# led-cpu-rev2.net
KiCad netlist of a schematic drawn in EAGLE
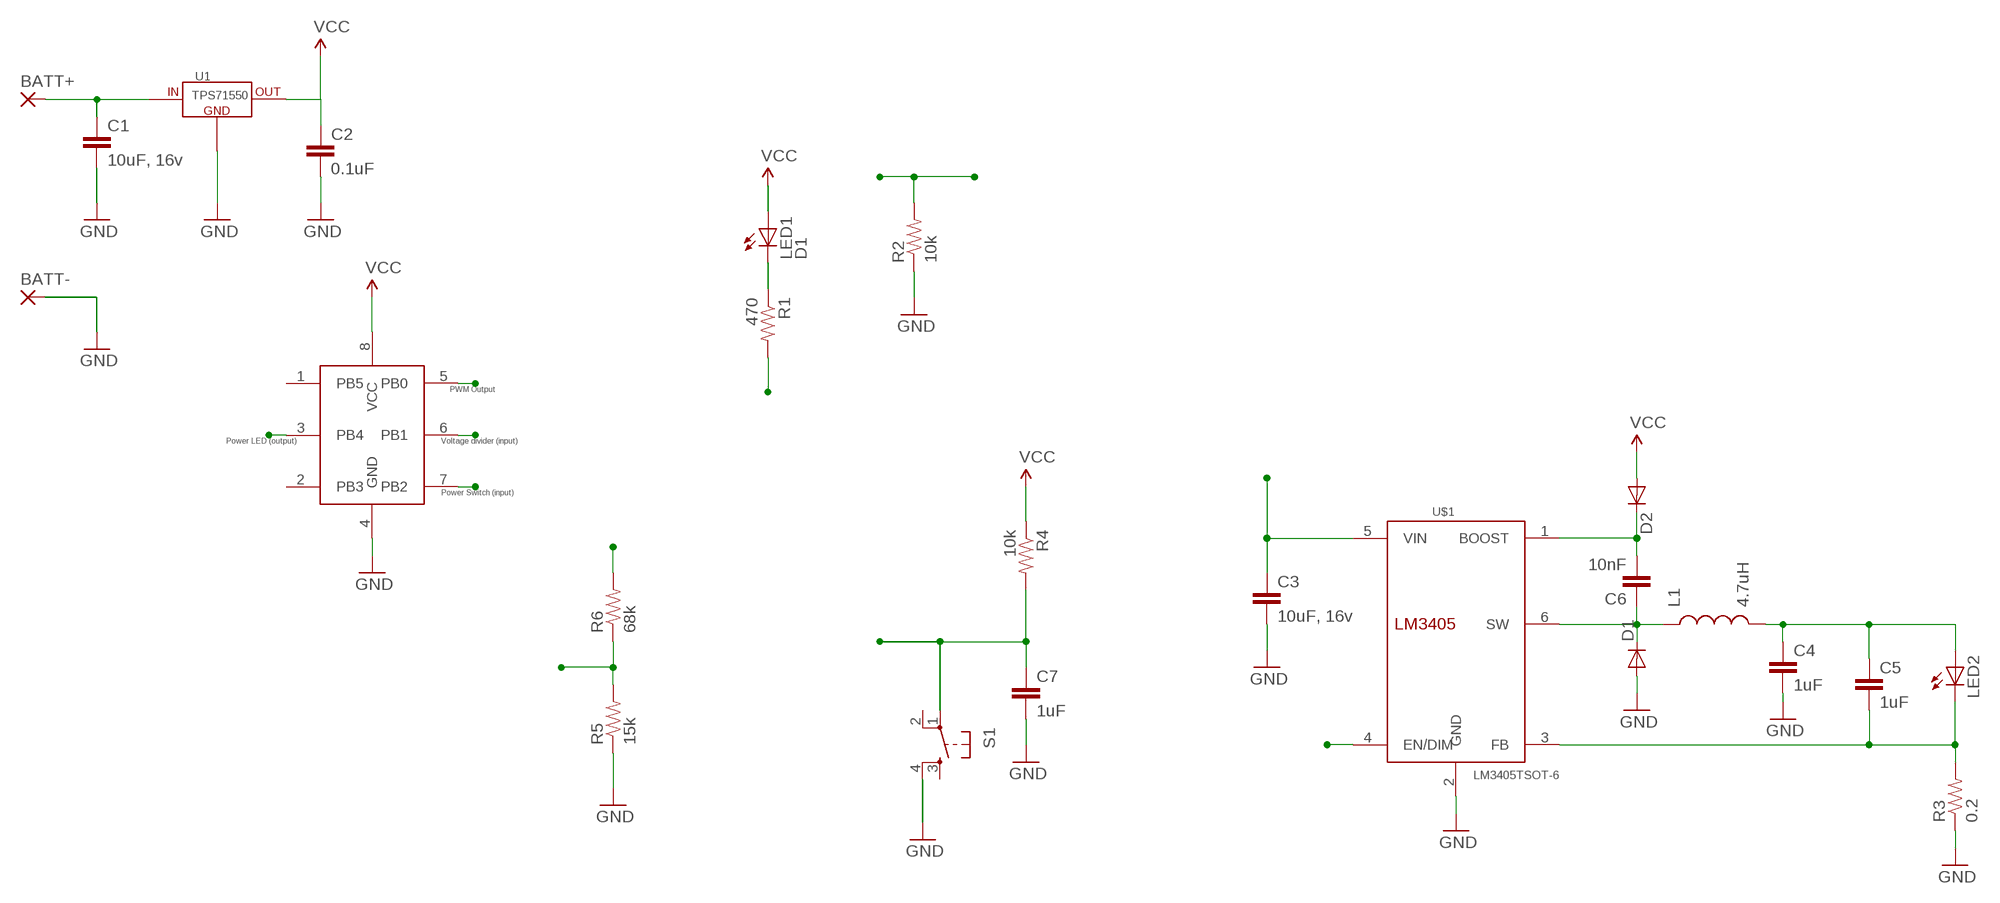
[diagram p0: schematic, sheet 1]

(export (version "E")
  (design (tool "Eeschema 10.0.6"))
  (components
    (comp (ref "BATT+")
      (value "SMD5")
      (footprint "eagle-import:SMD2,54-5,08")
      (libsource (lib "eagle-import") (part "SMD5"))
    )
    (comp (ref "BATT-")
      (value "SMD5")
      (footprint "eagle-import:SMD2,54-5,08")
      (libsource (lib "eagle-import") (part "SMD5"))
    )
    (comp (ref "C1")
      (value "10uF, 16v")
      (footprint "eagle-import:0805")
      (libsource (lib "eagle-import") (part "CAP0805"))
    )
    (comp (ref "C2")
      (value "0.1uF")
      (footprint "eagle-import:0805")
      (libsource (lib "eagle-import") (part "CAP0805"))
    )
    (comp (ref "C3")
      (value "10uF, 16v")
      (footprint "eagle-import:0805")
      (libsource (lib "eagle-import") (part "CAP0805"))
    )
    (comp (ref "C4")
      (value "1uF")
      (footprint "eagle-import:1206")
      (libsource (lib "eagle-import") (part "CAP1206"))
    )
    (comp (ref "C5")
      (value "1uF")
      (footprint "eagle-import:1206")
      (libsource (lib "eagle-import") (part "CAP1206"))
    )
    (comp (ref "C6")
      (value "10nF")
      (footprint "eagle-import:0805")
      (libsource (lib "eagle-import") (part "CAP0805"))
    )
    (comp (ref "C7")
      (value "1uF")
      (footprint "eagle-import:0805")
      (libsource (lib "eagle-import") (part "CAP0805"))
    )
    (comp (ref "D1")
      (value "DIODESMA")
      (footprint "eagle-import:SMA-DIODE")
      (libsource (lib "eagle-import") (part "DIODESMA"))
    )
    (comp (ref "D2")
      (value "DIODESOD")
      (footprint "eagle-import:SOD-323")
      (libsource (lib "eagle-import") (part "DIODESOD"))
    )
    (comp (ref "L1")
      (value "4.7uH")
      (footprint "eagle-import:1210")
      (libsource (lib "eagle-import") (part "INDUCTOR1210"))
    )
    (comp (ref "LED1")
      (value "D1")
      (footprint "eagle-import:CHIPLED_0603")
      (libsource (lib "eagle-import") (part "LEDCHIPLED_0603"))
    )
    (comp (ref "LED2")
      (value "LED3MM")
      (footprint "eagle-import:LED3MM")
      (libsource (lib "eagle-import") (part "LED3MM"))
    )
    (comp (ref "R1")
      (value "470")
      (footprint "eagle-import:0805")
      (libsource (lib "eagle-import") (part "RESISTOR0805-RES"))
    )
    (comp (ref "R2")
      (value "10k")
      (footprint "eagle-import:0805")
      (libsource (lib "eagle-import") (part "RESISTOR0805-RES"))
    )
    (comp (ref "R3")
      (value "0.2")
      (footprint "eagle-import:1206")
      (libsource (lib "eagle-import") (part "SparkFun-Resistors_RESISTOR1206"))
    )
    (comp (ref "R4")
      (value "10k")
      (footprint "eagle-import:0805")
      (libsource (lib "eagle-import") (part "RESISTOR0805-RES"))
    )
    (comp (ref "R5")
      (value "15k")
      (footprint "eagle-import:0805")
      (libsource (lib "eagle-import") (part "RESISTOR0805-RES"))
    )
    (comp (ref "R6")
      (value "68k")
      (footprint "eagle-import:0805")
      (libsource (lib "eagle-import") (part "RESISTOR0805-RES"))
    )
    (comp (ref "S1")
      (value "TAC_SWITCHPTH")
      (footprint "eagle-import:TACTILE-PTH")
      (libsource (lib "eagle-import") (part "TAC_SWITCHPTH"))
    )
    (comp (ref "U$1")
      (value "LM3405TSOT-6")
      (footprint "eagle-import:TSOT-6")
      (libsource (lib "eagle-import") (part "LM3405TSOT-6"))
    )
    (comp (ref "U1")
      (value "TPS71550")
      (footprint "eagle-import:SOT-23-5")
      (libsource (lib "eagle-import") (part "TPS715XX"))
    )
    (comp (ref "U2")
      (value "ATTINY13")
      (footprint "eagle-import:WSOIC-8")
      (libsource (lib "eagle-import") (part "ATTINY13"))
    )
  )
  (nets
    (net (code "1") (name "/BATT+") (class "Default")
      (node (ref "BATT+") (pin "1") (pinfunction "P_1") (pintype "passive"))
      (node (ref "C1") (pin "1") (pinfunction "1_1") (pintype "passive"))
      (node (ref "C3") (pin "1") (pinfunction "1_1") (pintype "passive"))
      (node (ref "R6") (pin "2") (pinfunction "2_2") (pintype "passive"))
      (node (ref "U$1") (pin "5") (pinfunction "VIN_5") (pintype "bidirectional"))
      (node (ref "U1") (pin "4") (pinfunction "IN_4") (pintype "bidirectional"))
    )
    (net (code "2") (name "/IND_LED_B") (class "Default")
      (node (ref "R1") (pin "2") (pinfunction "2_2") (pintype "passive"))
      (node (ref "U2") (pin "3") (pinfunction "PB4_3") (pintype "bidirectional"))
    )
    (net (code "3") (name "/PWM_OUT") (class "Default")
      (node (ref "R2") (pin "2") (pinfunction "2_2") (pintype "passive"))
      (node (ref "U$1") (pin "4") (pinfunction "EN/DIM_4") (pintype "bidirectional"))
      (node (ref "U2") (pin "5") (pinfunction "PB0_5") (pintype "bidirectional"))
    )
    (net (code "4") (name "/PWR_SW") (class "Default")
      (node (ref "C7") (pin "1") (pinfunction "1_1") (pintype "passive"))
      (node (ref "R4") (pin "2") (pinfunction "2_2") (pintype "passive"))
      (node (ref "S1") (pin "1") (pinfunction "1_1") (pintype "passive"))
      (node (ref "U2") (pin "7") (pinfunction "PB2_7") (pintype "bidirectional"))
    )
    (net (code "5") (name "/VDIV") (class "Default")
      (node (ref "R5") (pin "2") (pinfunction "2_2") (pintype "passive"))
      (node (ref "R6") (pin "1") (pinfunction "1_1") (pintype "passive"))
      (node (ref "U2") (pin "6") (pinfunction "PB1_6") (pintype "bidirectional"))
    )
    (net (code "6") (name "GND") (class "Default")
      (node (ref "BATT-") (pin "1") (pinfunction "P_1") (pintype "passive"))
      (node (ref "C1") (pin "2") (pinfunction "2_2") (pintype "passive"))
      (node (ref "C2") (pin "2") (pinfunction "2_2") (pintype "passive"))
      (node (ref "C3") (pin "2") (pinfunction "2_2") (pintype "passive"))
      (node (ref "C4") (pin "2") (pinfunction "2_2") (pintype "passive"))
      (node (ref "C7") (pin "2") (pinfunction "2_2") (pintype "passive"))
      (node (ref "D1") (pin "A") (pinfunction "A_A") (pintype "passive"))
      (node (ref "R2") (pin "1") (pinfunction "1_1") (pintype "passive"))
      (node (ref "R3") (pin "1") (pinfunction "1_1") (pintype "passive"))
      (node (ref "R5") (pin "1") (pinfunction "1_1") (pintype "passive"))
      (node (ref "S1") (pin "4") (pinfunction "4_4") (pintype "passive"))
      (node (ref "U$1") (pin "2") (pinfunction "GND_2") (pintype "bidirectional"))
      (node (ref "U1") (pin "2") (pinfunction "GND_2") (pintype "bidirectional"))
      (node (ref "U2") (pin "4") (pinfunction "GND_4") (pintype "bidirectional"))
    )
    (net (code "7") (name "Net-(C4-Pad1)") (class "Default")
      (node (ref "C4") (pin "1") (pinfunction "1_1") (pintype "passive"))
      (node (ref "C5") (pin "1") (pinfunction "1_1") (pintype "passive"))
      (node (ref "L1") (pin "2") (pinfunction "2_2") (pintype "passive"))
      (node (ref "LED2") (pin "A") (pinfunction "A_A") (pintype "passive"))
    )
    (net (code "8") (name "Net-(D2-C)") (class "Default")
      (node (ref "C6") (pin "2") (pinfunction "2_2") (pintype "passive"))
      (node (ref "D2") (pin "1") (pinfunction "C_1") (pintype "passive"))
      (node (ref "U$1") (pin "1") (pinfunction "BOOST_1") (pintype "bidirectional"))
    )
    (net (code "9") (name "Net-(LED1-PadC)") (class "Default")
      (node (ref "LED1") (pin "C") (pinfunction "C_C") (pintype "passive"))
      (node (ref "R1") (pin "1") (pinfunction "1_1") (pintype "passive"))
    )
    (net (code "10") (name "Net-(LED2-C)") (class "Default")
      (node (ref "C5") (pin "2") (pinfunction "2_2") (pintype "passive"))
      (node (ref "LED2") (pin "K") (pinfunction "C_K") (pintype "passive"))
      (node (ref "R3") (pin "2") (pinfunction "2_2") (pintype "passive"))
      (node (ref "U$1") (pin "3") (pinfunction "FB_3") (pintype "bidirectional"))
    )
    (net (code "11") (name "Net-(U$1-SW)") (class "Default")
      (node (ref "C6") (pin "1") (pinfunction "1_1") (pintype "passive"))
      (node (ref "D1") (pin "C") (pinfunction "C_C") (pintype "passive"))
      (node (ref "L1") (pin "1") (pinfunction "1_1") (pintype "passive"))
      (node (ref "U$1") (pin "6") (pinfunction "SW_6") (pintype "bidirectional"))
    )
    (net (code "12") (name "VCC") (class "Default")
      (node (ref "C2") (pin "1") (pinfunction "1_1") (pintype "passive"))
      (node (ref "D2") (pin "2") (pinfunction "A_2") (pintype "passive"))
      (node (ref "LED1") (pin "A") (pinfunction "A_A") (pintype "passive"))
      (node (ref "R4") (pin "1") (pinfunction "1_1") (pintype "passive"))
      (node (ref "U1") (pin "5") (pinfunction "OUT_5") (pintype "bidirectional"))
      (node (ref "U2") (pin "8") (pinfunction "VCC_8") (pintype "bidirectional"))
    )
    (net (code "13") (name "unconnected-(S1-Pad2)") (class "Default")
      (node (ref "S1") (pin "2") (pinfunction "2_2") (pintype "passive"))
    )
    (net (code "14") (name "unconnected-(S1-Pad3)") (class "Default")
      (node (ref "S1") (pin "3") (pinfunction "3_3") (pintype "passive"))
    )
    (net (code "15") (name "unconnected-(U2-PB3-Pad2)") (class "Default")
      (node (ref "U2") (pin "2") (pinfunction "PB3_2") (pintype "bidirectional"))
    )
    (net (code "16") (name "unconnected-(U2-PB5-Pad1)") (class "Default")
      (node (ref "U2") (pin "1") (pinfunction "PB5_1") (pintype "bidirectional"))
    )
  )
)
